# AM438x_EPOS_EVM_PMconnect_v2.net
KiCad netlist of a schematic drawn in Altium Designer
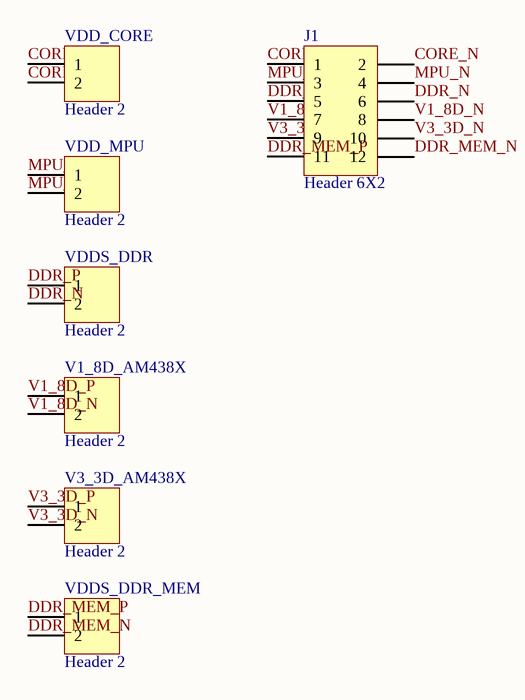
[diagram p0: AM438x_EPOS_EVM_PMconnect_v2.SchDoc]

(export (version "E")
  (design (tool "Eeschema 10.0.6"))
  (components
    (comp (ref "J1")
      (value "Header 6X2")
      (footprint "HDR2X6")
      (description "Header, 6-Pin, Dual row")
      (fields (field (name "PUBLISHER") "Altium Limited"))
      (libsource (lib "Miscellaneous Connectors") (part "Header 6X2"))
    )
    (comp (ref "V1_8D_AM438X")
      (value "Header 2")
      (footprint "HDR1X2")
      (description "Header, 2-Pin")
      (fields (field (name "PUBLISHER") "Altium Limited"))
      (libsource (lib "Miscellaneous Connectors") (part "Header 2"))
    )
    (comp (ref "V3_3D_AM438X")
      (value "Header 2")
      (footprint "HDR1X2")
      (description "Header, 2-Pin")
      (fields (field (name "PUBLISHER") "Altium Limited"))
      (libsource (lib "Miscellaneous Connectors") (part "Header 2"))
    )
    (comp (ref "VDDS_DDR")
      (value "Header 2")
      (footprint "HDR1X2")
      (description "Header, 2-Pin")
      (fields (field (name "PUBLISHER") "Altium Limited"))
      (libsource (lib "Miscellaneous Connectors") (part "Header 2"))
    )
    (comp (ref "VDDS_DDR_MEM")
      (value "Header 2")
      (footprint "HDR1X2")
      (description "Header, 2-Pin")
      (fields (field (name "PUBLISHER") "Altium Limited"))
      (libsource (lib "Miscellaneous Connectors") (part "Header 2"))
    )
    (comp (ref "VDD_CORE")
      (value "Header 2")
      (footprint "HDR1X2")
      (description "Header, 2-Pin")
      (fields (field (name "PUBLISHER") "Altium Limited"))
      (libsource (lib "Miscellaneous Connectors") (part "Header 2"))
    )
    (comp (ref "VDD_MPU")
      (value "Header 2")
      (footprint "HDR1X2")
      (description "Header, 2-Pin")
      (fields (field (name "PUBLISHER") "Altium Limited"))
      (libsource (lib "Miscellaneous Connectors") (part "Header 2"))
    )
  )
  (nets
    (net (code "1") (name "/CORE_N") (class "Default")
      (node (ref "J1") (pin "2") (pinfunction "2_2") (pintype "passive"))
      (node (ref "VDD_CORE") (pin "2") (pinfunction "2_2") (pintype "passive"))
    )
    (net (code "2") (name "/CORE_P") (class "Default")
      (node (ref "J1") (pin "1") (pinfunction "1_1") (pintype "passive"))
      (node (ref "VDD_CORE") (pin "1") (pinfunction "1_1") (pintype "passive"))
    )
    (net (code "3") (name "/DDR_MEM_N") (class "Default")
      (node (ref "J1") (pin "12") (pinfunction "12_12") (pintype "passive"))
      (node (ref "VDDS_DDR_MEM") (pin "2") (pinfunction "2_2") (pintype "passive"))
    )
    (net (code "4") (name "/DDR_MEM_P") (class "Default")
      (node (ref "J1") (pin "11") (pinfunction "11_11") (pintype "passive"))
      (node (ref "VDDS_DDR_MEM") (pin "1") (pinfunction "1_1") (pintype "passive"))
    )
    (net (code "5") (name "/DDR_N") (class "Default")
      (node (ref "J1") (pin "6") (pinfunction "6_6") (pintype "passive"))
      (node (ref "VDDS_DDR") (pin "2") (pinfunction "2_2") (pintype "passive"))
    )
    (net (code "6") (name "/DDR_P") (class "Default")
      (node (ref "J1") (pin "5") (pinfunction "5_5") (pintype "passive"))
      (node (ref "VDDS_DDR") (pin "1") (pinfunction "1_1") (pintype "passive"))
    )
    (net (code "7") (name "/MPU_N") (class "Default")
      (node (ref "J1") (pin "4") (pinfunction "4_4") (pintype "passive"))
      (node (ref "VDD_MPU") (pin "2") (pinfunction "2_2") (pintype "passive"))
    )
    (net (code "8") (name "/MPU_P") (class "Default")
      (node (ref "J1") (pin "3") (pinfunction "3_3") (pintype "passive"))
      (node (ref "VDD_MPU") (pin "1") (pinfunction "1_1") (pintype "passive"))
    )
    (net (code "9") (name "/V1_8D_N") (class "Default")
      (node (ref "J1") (pin "8") (pinfunction "8_8") (pintype "passive"))
      (node (ref "V1_8D_AM438X") (pin "2") (pinfunction "2_2") (pintype "passive"))
    )
    (net (code "10") (name "/V1_8D_P") (class "Default")
      (node (ref "J1") (pin "7") (pinfunction "7_7") (pintype "passive"))
      (node (ref "V1_8D_AM438X") (pin "1") (pinfunction "1_1") (pintype "passive"))
    )
    (net (code "11") (name "/V3_3D_N") (class "Default")
      (node (ref "J1") (pin "10") (pinfunction "10_10") (pintype "passive"))
      (node (ref "V3_3D_AM438X") (pin "2") (pinfunction "2_2") (pintype "passive"))
    )
    (net (code "12") (name "/V3_3D_P") (class "Default")
      (node (ref "J1") (pin "9") (pinfunction "9_9") (pintype "passive"))
      (node (ref "V3_3D_AM438X") (pin "1") (pinfunction "1_1") (pintype "passive"))
    )
  )
)
